# Motor_Driver_and_Encoder.net
KiCad netlist of a schematic drawn in Altium Designer
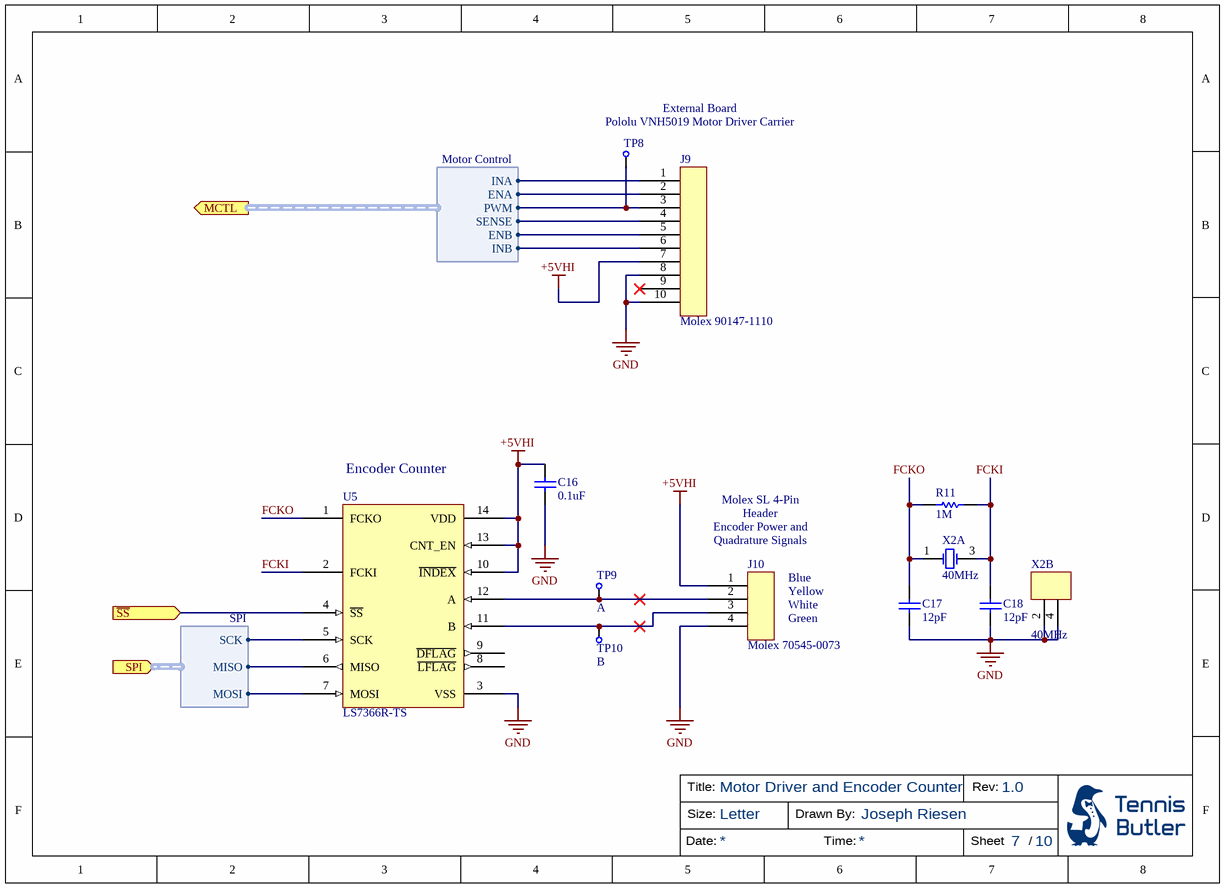
[diagram p0: Motor Driver and Encoder.SchDoc]

(export (version "E")
  (design (tool "Eeschema 10.0.6"))
  (components
    (comp (ref "C16")
      (value "0.1uF")
      (footprint "CAPC0805(2012)100_M")
      (description "CAP 100nF 6.3V ±10% 0805 (2012 Metric) Thickness 1mm SMD")
      (fields (field (name "TOLERANCE") "Â±10%"))
      (libsource (lib "Altium Content Vault") (part "CAP"))
    )
    (comp (ref "C17")
      (value "12pF")
      (footprint "CAPC1608X87X35ML15T15")
      (fields (field (name "MANUFACTURER") "Kemet") (field (name "PART NUMBER") "C0603C120C5GACTU"))
      (libsource (lib "Altium Content Vault") (part "CAP"))
    )
    (comp (ref "C18")
      (value "12pF")
      (footprint "CAPC1608X87X35ML15T15")
      (fields (field (name "MANUFACTURER") "Kemet") (field (name "PART NUMBER") "C0603C120C5GACTU"))
      (libsource (lib "Altium Content Vault") (part "CAP"))
    )
    (comp (ref "J9")
      (value "Molex 90147-1110")
      (footprint "Molex 90147-1110")
      (description "C-Grid® PC Board Connector, Single Row, Vertical, 10 Circuits, Tin (Sn) Plating")
      (fields (field (name "MANUFACTURER") "Molex") (field (name "MANUFACTURER PART NUMBER") "90147-1110"))
      (libsource (lib "TennisButler") (part "Molex 90147-1110 C-Grid 10-Pin Header"))
    )
    (comp (ref "J10")
      (value "Molex 70545-0073")
      (footprint "Molex 70545-0073")
      (description "CONN HEADER VERT 4POS 2.54MM, PEG")
      (fields (field (name "MANUFACTURER") "Molex") (field (name "MANUFACTURER PART NUMBER") "70545-0073"))
      (libsource (lib "TennisButler") (part "Molex 70545-0073 SL 4-Pin Header"))
    )
    (comp (ref "R11")
      (value "1M")
      (footprint "RESC2013X70X40NL20T20")
      (fields (field (name "MANUFACTURER") "Panasonic"))
      (libsource (lib "Altium Content Vault") (part "RES-2"))
    )
    (comp (ref "TP8")
      (value "PWM")
      (footprint "Test Point")
      (libsource (lib "Miscellaneous") (part "Test Point"))
    )
    (comp (ref "TP9")
      (value "A")
      (footprint "Test Point")
      (libsource (lib "Miscellaneous") (part "Test Point"))
    )
    (comp (ref "TP10")
      (value "B")
      (footprint "Test Point")
      (libsource (lib "Miscellaneous") (part "Test Point"))
    )
    (comp (ref "U5")
      (value "LS7366R-TS")
      (footprint "TSOP65P640X110-14M")
      (description "32-Bit Quadrature Clock Counter with Serial Interface")
      (fields (field (name "MANUFACTURER") "LSI/CSI"))
      (libsource (lib "LS7366R-TS") (part "LS7366R-TS"))
    )
    (comp (ref "X2")
      (value "40MHz")
      (footprint "DFN220P320X80-4M")
      (description "CRYSTAL 40MHZ 12PF SMD")
      (fields
        (field (name "MANUFACTURER") "Fox Electronics")
        (field (name "MANUFACTURER PART NUMBER") "603-40-48")
      )
      (libsource (lib "") (part "603-40-48_1"))
    )
  )
  (nets
    (net (code "4") (name "+5VHI") (class "Default")
      (node (ref "C16") (pin "2") (pinfunction "2_2") (pintype "passive"))
      (node (ref "J10") (pin "1") (pintype "passive"))
      (node (ref "J9") (pin "7") (pintype "passive"))
      (node (ref "U5") (pin "10") (pinfunction "~{INDEX}_10") (pintype "input"))
      (node (ref "U5") (pin "13") (pinfunction "CNT_EN_13") (pintype "input"))
      (node (ref "U5") (pin "14") (pinfunction "VDD_14") (pintype "power_in"))
    )
    (net (code "5") (name "/ENA") (class "Default") (node (ref "J9") (pin "2") (pintype "passive")))
    (net (code "6") (name "/ENB") (class "Default") (node (ref "J9") (pin "5") (pintype "passive")))
    (net (code "7") (name "/FCKI") (class "Default")
      (node (ref "C18") (pin "2") (pinfunction "2_2") (pintype "passive"))
      (node (ref "R11") (pin "1") (pinfunction "1_1") (pintype "passive"))
      (node (ref "U5") (pin "2") (pinfunction "FCKI_2") (pintype "passive"))
      (node (ref "X2") (pin "3") (pinfunction "X2_3") (pintype "passive"))
    )
    (net (code "8") (name "/FCKO") (class "Default")
      (node (ref "C17") (pin "2") (pinfunction "2_2") (pintype "passive"))
      (node (ref "R11") (pin "2") (pinfunction "2_2") (pintype "passive"))
      (node (ref "U5") (pin "1") (pinfunction "FCKO_1") (pintype "passive"))
      (node (ref "X2") (pin "1") (pinfunction "X1_1") (pintype "passive"))
    )
    (net (code "9") (name "/INA") (class "Default") (node (ref "J9") (pin "1") (pintype "passive")))
    (net (code "10") (name "/INB") (class "Default") (node (ref "J9") (pin "6") (pintype "passive")))
    (net (code "11") (name "/MISO") (class "Default")
      (node (ref "U5") (pin "6") (pinfunction "MISO_6") (pintype "output"))
    )
    (net (code "12") (name "/MOSI") (class "Default")
      (node (ref "U5") (pin "7") (pinfunction "MOSI_7") (pintype "input"))
    )
    (net (code "13") (name "/PWM") (class "Default")
      (node (ref "J9") (pin "3") (pintype "passive"))
      (node (ref "TP8") (pin "1") (pinfunction "1_1") (pintype "passive"))
    )
    (net (code "14") (name "/SCK") (class "Default")
      (node (ref "U5") (pin "5") (pinfunction "SCK_5") (pintype "input"))
    )
    (net (code "15") (name "/SENSE") (class "Default") (node (ref "J9") (pin "4") (pintype "passive")))
    (net (code "18") (name "/~{SS}") (class "Default")
      (node (ref "U5") (pin "4") (pinfunction "~{SS}_4") (pintype "input"))
    )
    (net (code "19") (name "GND") (class "Default")
      (node (ref "C16") (pin "1") (pinfunction "1_1") (pintype "passive"))
      (node (ref "C17") (pin "1") (pinfunction "1_1") (pintype "passive"))
      (node (ref "C18") (pin "1") (pinfunction "1_1") (pintype "passive"))
      (node (ref "J10") (pin "4") (pintype "passive"))
      (node (ref "J9") (pin "10") (pintype "passive"))
      (node (ref "J9") (pin "8") (pintype "passive"))
      (node (ref "U5") (pin "3") (pinfunction "VSS_3") (pintype "power_in"))
      (node (ref "X2") (pin "2") (pinfunction "GND_2") (pintype "power_in"))
      (node (ref "X2") (pin "4") (pinfunction "GND_4") (pintype "power_in"))
    )
    (net (code "20") (name "Net-(U5-A)") (class "Default")
      (node (ref "J10") (pin "2") (pintype "passive"))
      (node (ref "TP9") (pin "1") (pinfunction "1_1") (pintype "passive"))
      (node (ref "U5") (pin "12") (pinfunction "A_12") (pintype "input"))
    )
    (net (code "21") (name "Net-(U5-B)") (class "Default")
      (node (ref "J10") (pin "3") (pintype "passive"))
      (node (ref "TP10") (pin "1") (pinfunction "1_1") (pintype "passive"))
      (node (ref "U5") (pin "11") (pinfunction "B_11") (pintype "input"))
    )
    (net (code "22") (name "unconnected-(J9-Pad9)") (class "Default")
      (node (ref "J9") (pin "9") (pintype "passive+no_connect"))
    )
    (net (code "23") (name "unconnected-(U5-~{DFLAG}-Pad9)") (class "Default")
      (node (ref "U5") (pin "9") (pinfunction "~{DFLAG}_9") (pintype "output"))
    )
    (net (code "24") (name "unconnected-(U5-~{LFLAG}-Pad8)") (class "Default")
      (node (ref "U5") (pin "8") (pinfunction "~{LFLAG}_8") (pintype "output"))
    )
  )
)
